# TL494.net
KiCad netlist of a schematic drawn in Altium Designer
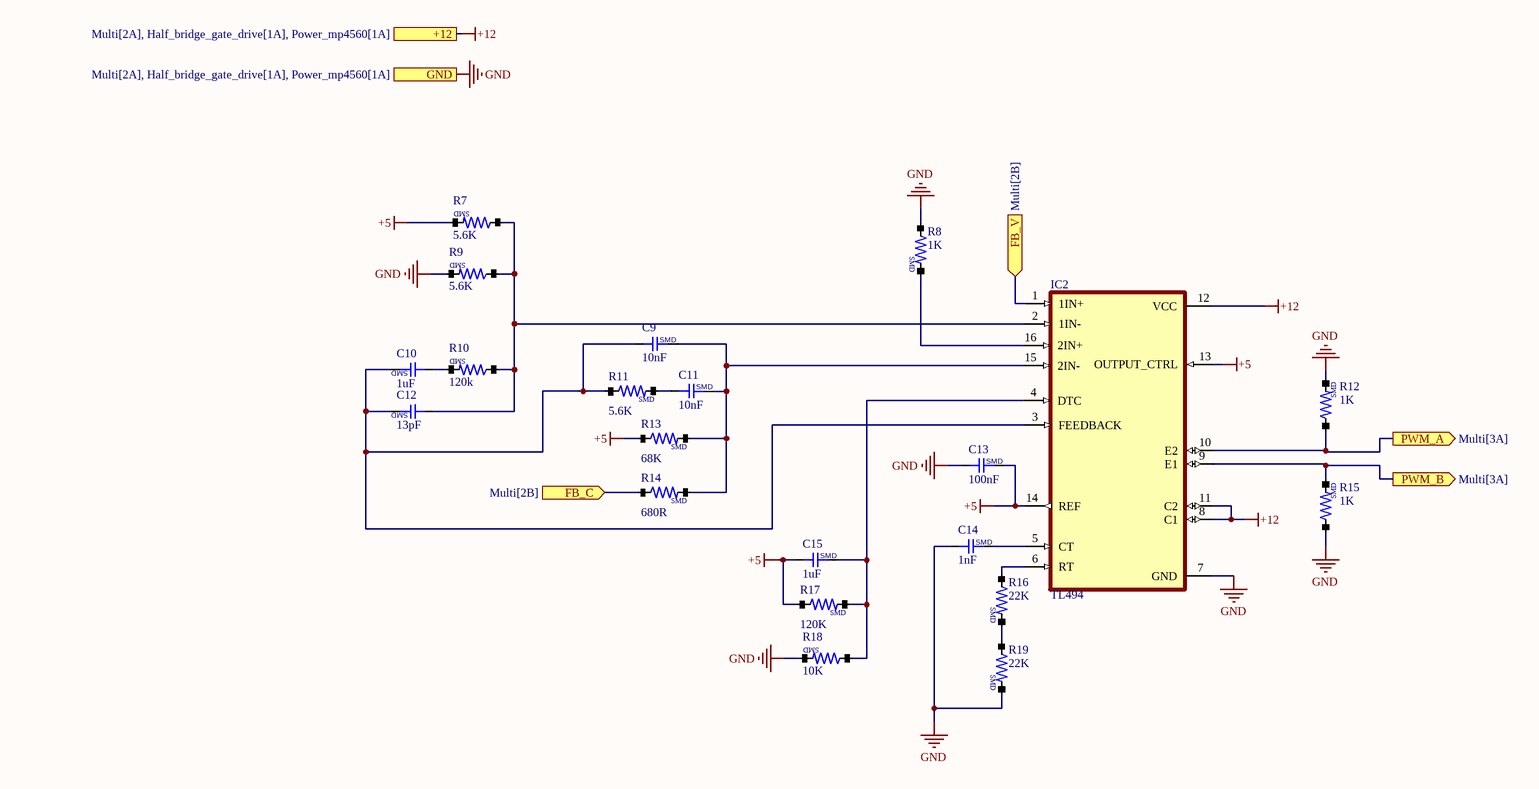
[diagram p0: TL494.SchDoc]

(export (version "E")
  (design (tool "Eeschema 10.0.6"))
  (components
    (comp (ref "C9") (value "10nF") (footprint "CAP-0603") (libsource (lib "kave-eng-pro") (part "cap_smd")))
    (comp (ref "C10") (value "1uF") (footprint "CAP-0603") (libsource (lib "") (part "cap_smd_1")))
    (comp (ref "C11") (value "10nF") (footprint "CAP-0603") (libsource (lib "kave-eng-pro") (part "cap_smd")))
    (comp (ref "C12") (value "13pF") (footprint "CAP-0603") (libsource (lib "") (part "cap_smd_1")))
    (comp (ref "C13") (value "100nF") (footprint "CAP-0603") (libsource (lib "") (part "cap_smd_1")))
    (comp (ref "C14") (value "1nF") (footprint "CAP-0603") (libsource (lib "kave-eng-pro") (part "cap_smd")))
    (comp (ref "C15") (value "1uF") (footprint "CAP-0805") (libsource (lib "") (part "cap_smd_1")))
    (comp (ref "IC2") (value "TL494") (footprint "TL494_SMD") (libsource (lib "kave-eng-pro") (part "TL494")))
    (comp (ref "R7") (value "5.6K") (footprint "RES/0603") (libsource (lib "") (part "RES/SMD_3")))
    (comp (ref "R8") (value "1K") (footprint "RES/0603") (libsource (lib "kave-eng-pro") (part "RES/SMD")))
    (comp (ref "R9") (value "5.6K") (footprint "RES/0603") (libsource (lib "") (part "RES/SMD_3")))
    (comp (ref "R10") (value "120k") (footprint "RES/0603") (libsource (lib "") (part "RES/SMD_3")))
    (comp (ref "R11") (value "5.6K") (footprint "RES/0603") (libsource (lib "") (part "RES/SMD_2")))
    (comp (ref "R12") (value "1K") (footprint "RES/0603") (libsource (lib "") (part "RES/SMD_4")))
    (comp (ref "R13") (value "68K") (footprint "RES/0603") (libsource (lib "") (part "RES/SMD_1")))
    (comp (ref "R14") (value "680R") (footprint "RES/0603") (libsource (lib "") (part "RES/SMD_1")))
    (comp (ref "R15") (value "1K") (footprint "RES/0603") (libsource (lib "") (part "RES/SMD_4")))
    (comp (ref "R16") (value "22K") (footprint "RES/0603") (libsource (lib "kave-eng-pro") (part "RES/SMD")))
    (comp (ref "R17") (value "120K") (footprint "RES/0603") (libsource (lib "") (part "RES/SMD_1")))
    (comp (ref "R18") (value "10K") (footprint "RES/0603") (libsource (lib "") (part "RES/SMD_3")))
    (comp (ref "R19") (value "22K") (footprint "RES/0603") (libsource (lib "kave-eng-pro") (part "RES/SMD")))
  )
  (nets
    (net (code "1") (name "+5") (class "Default")
      (node (ref "C13") (pin "2") (pintype "passive"))
      (node (ref "C15") (pin "1") (pintype "passive"))
      (node (ref "IC2") (pin "13") (pinfunction "OUTPUT_CTRL_13") (pintype "input"))
      (node (ref "IC2") (pin "14") (pinfunction "REF_14") (pintype "output"))
      (node (ref "R13") (pin "1") (pinfunction "1_1") (pintype "passive"))
      (node (ref "R17") (pin "1") (pinfunction "1_1") (pintype "passive"))
      (node (ref "R7") (pin "2") (pinfunction "2_2") (pintype "passive"))
    )
    (net (code "2") (name "+12") (class "Default")
      (node (ref "IC2") (pin "11") (pinfunction "C2_11") (pintype "bidirectional"))
      (node (ref "IC2") (pin "12") (pinfunction "VCC_12") (pintype "power_in"))
      (node (ref "IC2") (pin "8") (pinfunction "C1_8") (pintype "bidirectional"))
    )
    (net (code "3") (name "/FB_C") (class "Default")
      (node (ref "R14") (pin "1") (pinfunction "1_1") (pintype "passive"))
    )
    (net (code "4") (name "/FB_V") (class "Default")
      (node (ref "IC2") (pin "1") (pinfunction "1IN+_1") (pintype "input"))
    )
    (net (code "5") (name "/PWM_A") (class "Default")
      (node (ref "IC2") (pin "10") (pinfunction "E2_10") (pintype "bidirectional"))
      (node (ref "R12") (pin "1") (pinfunction "1_1") (pintype "passive"))
    )
    (net (code "6") (name "/PWM_B") (class "Default")
      (node (ref "IC2") (pin "9") (pinfunction "E1_9") (pintype "bidirectional"))
      (node (ref "R15") (pin "2") (pinfunction "2_2") (pintype "passive"))
    )
    (net (code "7") (name "GND") (class "Default")
      (node (ref "C13") (pin "1") (pintype "passive"))
      (node (ref "C14") (pin "1") (pintype "passive"))
      (node (ref "IC2") (pin "7") (pinfunction "GND_7") (pintype "power_in"))
      (node (ref "R12") (pin "2") (pinfunction "2_2") (pintype "passive"))
      (node (ref "R15") (pin "1") (pinfunction "1_1") (pintype "passive"))
      (node (ref "R18") (pin "2") (pinfunction "2_2") (pintype "passive"))
      (node (ref "R19") (pin "2") (pinfunction "2_2") (pintype "passive"))
      (node (ref "R8") (pin "1") (pinfunction "1_1") (pintype "passive"))
      (node (ref "R9") (pin "2") (pinfunction "2_2") (pintype "passive"))
    )
    (net (code "8") (name "Net-(C10-Pad1)") (class "Default")
      (node (ref "C10") (pin "1") (pintype "passive"))
      (node (ref "R10") (pin "2") (pinfunction "2_2") (pintype "passive"))
    )
    (net (code "9") (name "Net-(C11-Pad1)") (class "Default")
      (node (ref "C11") (pin "1") (pintype "passive"))
      (node (ref "R11") (pin "2") (pinfunction "2_2") (pintype "passive"))
    )
    (net (code "10") (name "Net-(IC2-1IN-)") (class "Default")
      (node (ref "C12") (pin "1") (pintype "passive"))
      (node (ref "IC2") (pin "2") (pinfunction "1IN-_2") (pintype "input"))
      (node (ref "R10") (pin "1") (pinfunction "1_1") (pintype "passive"))
      (node (ref "R7") (pin "1") (pinfunction "1_1") (pintype "passive"))
      (node (ref "R9") (pin "1") (pinfunction "1_1") (pintype "passive"))
    )
    (net (code "11") (name "Net-(IC2-2IN+)") (class "Default")
      (node (ref "IC2") (pin "16") (pinfunction "2IN+_16") (pintype "input"))
      (node (ref "R8") (pin "2") (pinfunction "2_2") (pintype "passive"))
    )
    (net (code "12") (name "Net-(IC2-2IN-)") (class "Default")
      (node (ref "C11") (pin "2") (pintype "passive"))
      (node (ref "C9") (pin "2") (pintype "passive"))
      (node (ref "IC2") (pin "15") (pinfunction "2IN-_15") (pintype "input"))
      (node (ref "R13") (pin "2") (pinfunction "2_2") (pintype "passive"))
      (node (ref "R14") (pin "2") (pinfunction "2_2") (pintype "passive"))
    )
    (net (code "13") (name "Net-(IC2-CT)") (class "Default")
      (node (ref "C14") (pin "2") (pintype "passive"))
      (node (ref "IC2") (pin "5") (pinfunction "CT_5") (pintype "input"))
    )
    (net (code "14") (name "Net-(IC2-DTC)") (class "Default")
      (node (ref "C15") (pin "2") (pintype "passive"))
      (node (ref "IC2") (pin "4") (pinfunction "DTC_4") (pintype "input"))
      (node (ref "R17") (pin "2") (pinfunction "2_2") (pintype "passive"))
      (node (ref "R18") (pin "1") (pinfunction "1_1") (pintype "passive"))
    )
    (net (code "15") (name "Net-(IC2-FEEDBACK)") (class "Default")
      (node (ref "C10") (pin "2") (pintype "passive"))
      (node (ref "C12") (pin "2") (pintype "passive"))
      (node (ref "C9") (pin "1") (pintype "passive"))
      (node (ref "IC2") (pin "3") (pinfunction "FEEDBACK_3") (pintype "input"))
      (node (ref "R11") (pin "1") (pinfunction "1_1") (pintype "passive"))
    )
    (net (code "16") (name "Net-(IC2-RT)") (class "Default")
      (node (ref "IC2") (pin "6") (pinfunction "RT_6") (pintype "input"))
      (node (ref "R16") (pin "1") (pinfunction "1_1") (pintype "passive"))
    )
    (net (code "17") (name "Net-(R16-Pad2)") (class "Default")
      (node (ref "R16") (pin "2") (pinfunction "2_2") (pintype "passive"))
      (node (ref "R19") (pin "1") (pinfunction "1_1") (pintype "passive"))
    )
  )
)
